# box1LEDS.net
KiCad netlist of a schematic drawn in EAGLE
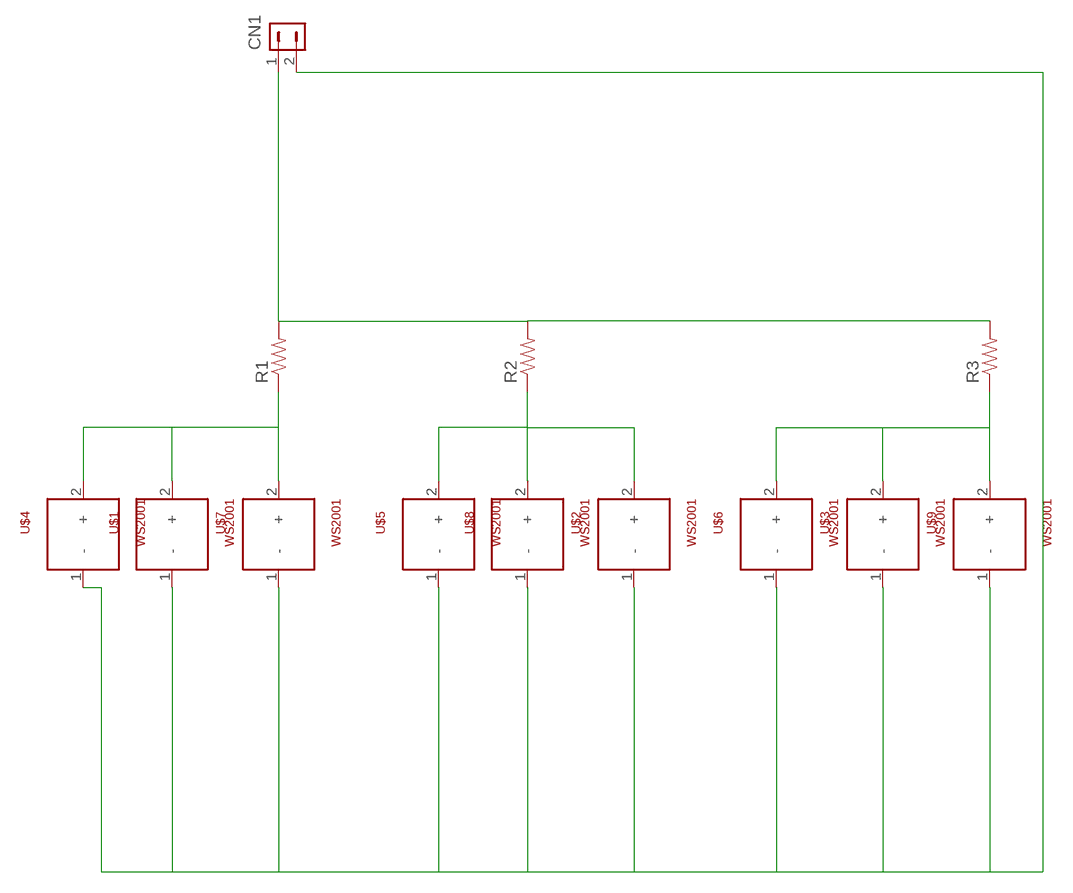
[diagram p0: schematic, sheet 1]

(export (version "E")
  (design (tool "Eeschema 10.0.6"))
  (components
    (comp (ref "CN1")
      (value "HDR-1X2-SIP-100")
      (footprint "eagle-import:SIP-100-2V")
      (libsource (lib "eagle-import") (part "HDR-1X2-SIP-100"))
    )
    (comp (ref "R1")
      (value "RESISTORPTH-1/4W")
      (footprint "eagle-import:AXIAL-0.4")
      (libsource (lib "eagle-import") (part "RESISTORPTH-1/4W"))
    )
    (comp (ref "R2")
      (value "RESISTORPTH-1/4W")
      (footprint "eagle-import:AXIAL-0.4")
      (libsource (lib "eagle-import") (part "RESISTORPTH-1/4W"))
    )
    (comp (ref "R3")
      (value "RESISTORPTH-1/4W")
      (footprint "eagle-import:AXIAL-0.4")
      (libsource (lib "eagle-import") (part "RESISTORPTH-1/4W"))
    )
    (comp (ref "U$1")
      (value "WS2001")
      (footprint "eagle-import:WH2001")
      (libsource (lib "eagle-import") (part "WS2001"))
    )
    (comp (ref "U$2")
      (value "WS2001")
      (footprint "eagle-import:WH2001")
      (libsource (lib "eagle-import") (part "WS2001"))
    )
    (comp (ref "U$3")
      (value "WS2001")
      (footprint "eagle-import:WH2001")
      (libsource (lib "eagle-import") (part "WS2001"))
    )
    (comp (ref "U$4")
      (value "WS2001")
      (footprint "eagle-import:WH2001")
      (libsource (lib "eagle-import") (part "WS2001"))
    )
    (comp (ref "U$5")
      (value "WS2001")
      (footprint "eagle-import:WH2001")
      (libsource (lib "eagle-import") (part "WS2001"))
    )
    (comp (ref "U$6")
      (value "WS2001")
      (footprint "eagle-import:WH2001")
      (libsource (lib "eagle-import") (part "WS2001"))
    )
    (comp (ref "U$7")
      (value "WS2001")
      (footprint "eagle-import:WH2001")
      (libsource (lib "eagle-import") (part "WS2001"))
    )
    (comp (ref "U$8")
      (value "WS2001")
      (footprint "eagle-import:WH2001")
      (libsource (lib "eagle-import") (part "WS2001"))
    )
    (comp (ref "U$9")
      (value "WS2001")
      (footprint "eagle-import:WH2001")
      (libsource (lib "eagle-import") (part "WS2001"))
    )
  )
  (nets
    (net (code "1") (name "Net-(R1-1)") (class "Default")
      (node (ref "R1") (pin "P$1") (pinfunction "1_P$1") (pintype "passive"))
      (node (ref "U$1") (pin "2") (pinfunction "+_2") (pintype "bidirectional"))
      (node (ref "U$4") (pin "2") (pinfunction "+_2") (pintype "bidirectional"))
      (node (ref "U$7") (pin "2") (pinfunction "+_2") (pintype "bidirectional"))
    )
    (net (code "2") (name "Net-(R1-2)") (class "Default")
      (node (ref "CN1") (pin "1") (pinfunction "1_1") (pintype "passive"))
      (node (ref "R1") (pin "P$2") (pinfunction "2_P$2") (pintype "passive"))
      (node (ref "R2") (pin "P$2") (pinfunction "2_P$2") (pintype "passive"))
      (node (ref "R3") (pin "P$2") (pinfunction "2_P$2") (pintype "passive"))
    )
    (net (code "3") (name "Net-(R2-1)") (class "Default")
      (node (ref "R2") (pin "P$1") (pinfunction "1_P$1") (pintype "passive"))
      (node (ref "U$2") (pin "2") (pinfunction "+_2") (pintype "bidirectional"))
      (node (ref "U$5") (pin "2") (pinfunction "+_2") (pintype "bidirectional"))
      (node (ref "U$8") (pin "2") (pinfunction "+_2") (pintype "bidirectional"))
    )
    (net (code "4") (name "Net-(R3-1)") (class "Default")
      (node (ref "R3") (pin "P$1") (pinfunction "1_P$1") (pintype "passive"))
      (node (ref "U$3") (pin "2") (pinfunction "+_2") (pintype "bidirectional"))
      (node (ref "U$6") (pin "2") (pinfunction "+_2") (pintype "bidirectional"))
      (node (ref "U$9") (pin "2") (pinfunction "+_2") (pintype "bidirectional"))
    )
    (net (code "5") (name "Net-(U$1--)") (class "Default")
      (node (ref "CN1") (pin "2") (pinfunction "2_2") (pintype "passive"))
      (node (ref "U$1") (pin "1") (pinfunction "-_1") (pintype "bidirectional"))
      (node (ref "U$2") (pin "1") (pinfunction "-_1") (pintype "bidirectional"))
      (node (ref "U$3") (pin "1") (pinfunction "-_1") (pintype "bidirectional"))
      (node (ref "U$4") (pin "1") (pinfunction "-_1") (pintype "bidirectional"))
      (node (ref "U$5") (pin "1") (pinfunction "-_1") (pintype "bidirectional"))
      (node (ref "U$6") (pin "1") (pinfunction "-_1") (pintype "bidirectional"))
      (node (ref "U$7") (pin "1") (pinfunction "-_1") (pintype "bidirectional"))
      (node (ref "U$8") (pin "1") (pinfunction "-_1") (pintype "bidirectional"))
      (node (ref "U$9") (pin "1") (pinfunction "-_1") (pintype "bidirectional"))
    )
  )
)
